# KUBODriver_Bridge.net
KiCad netlist of a schematic drawn in Altium Designer
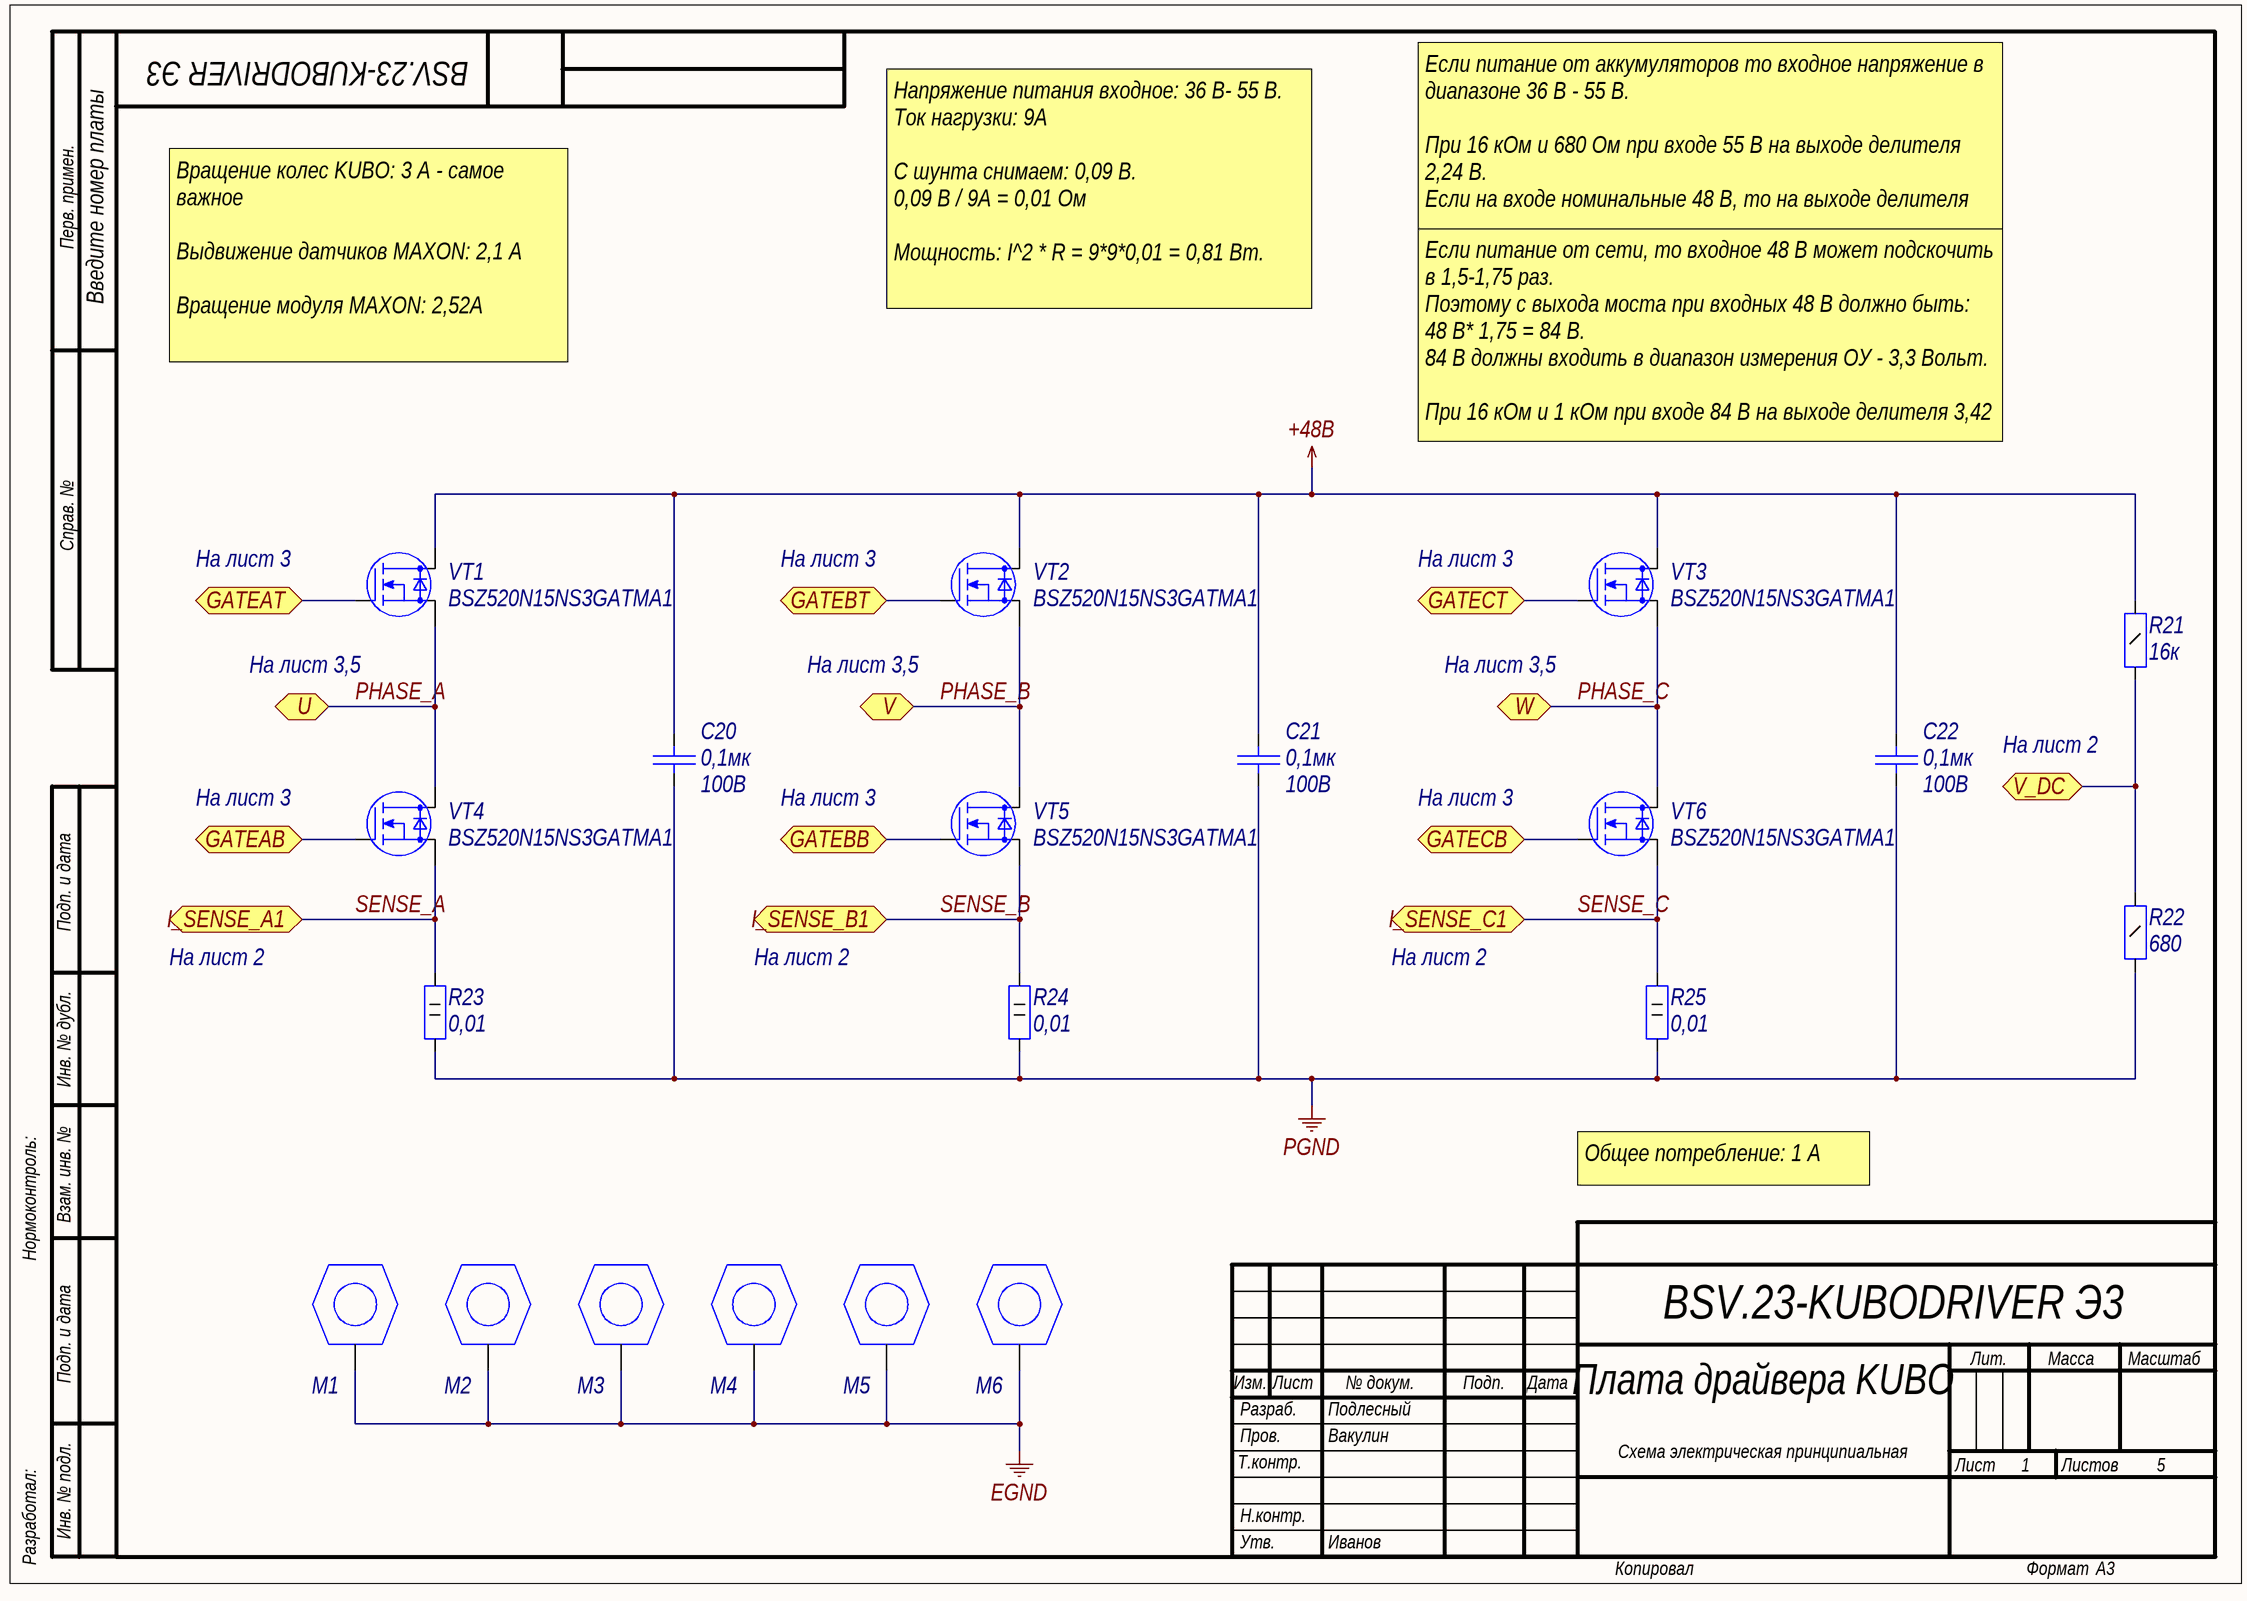
[diagram p0: KUBODriver_Bridge.SchDoc]

(export (version "E")
  (design (tool "Eeschema 10.0.6"))
  (components
    (comp (ref "C20")
      (value "0,1мк")
      (footprint "C1206")
      (description "Конденсатор")
      (fields (field (name "VOLTAGE") "100В") (field (name "PART NUMBER") "GRM31C5C2A104JA01L "))
      (libsource (lib "MOP44") (part "Capacitor"))
    )
    (comp (ref "C21")
      (value "0,1мк")
      (footprint "C1206")
      (description "Конденсатор")
      (fields (field (name "VOLTAGE") "100В") (field (name "PART NUMBER") "GRM31C5C2A104JA01L "))
      (libsource (lib "MOP44") (part "Capacitor"))
    )
    (comp (ref "C22")
      (value "0,1мк")
      (footprint "C1206")
      (description "Конденсатор")
      (fields (field (name "VOLTAGE") "100В") (field (name "PART NUMBER") "GRM31C5C2A104JA01L "))
      (libsource (lib "MOP44") (part "Capacitor"))
    )
    (comp (ref "M1") (value "SCREW") (footprint "SCREW3") (libsource (lib "MOP44") (part "SCREW")))
    (comp (ref "M2") (value "SCREW") (footprint "SCREW3") (libsource (lib "MOP44") (part "SCREW")))
    (comp (ref "M3") (value "SCREW") (footprint "SCREW3") (libsource (lib "MOP44") (part "SCREW")))
    (comp (ref "M4") (value "SCREW") (footprint "SCREW3") (libsource (lib "MOP44") (part "SCREW")))
    (comp (ref "M5") (value "SCREW") (footprint "SCREW3") (libsource (lib "MOP44") (part "SCREW")))
    (comp (ref "M6") (value "SCREW") (footprint "SCREW3") (libsource (lib "MOP44") (part "SCREW")))
    (comp (ref "R21")
      (value "16к")
      (footprint "R1206")
      (description "Резистор")
      (fields (field (name "PART NUMBER") "RC1206FR-0716KL") (field (name "POWER") "0,25Вт"))
      (libsource (lib "MOP44") (part "Resistor_0,25Вт"))
    )
    (comp (ref "R22")
      (value "680")
      (footprint "R1206")
      (description "Резистор")
      (fields (field (name "PART NUMBER") "RC1206FR-07680RL") (field (name "POWER") "0,25Вт"))
      (libsource (lib "MOP44") (part "Resistor_0,25Вт"))
    )
    (comp (ref "R23")
      (value "0,01")
      (footprint "R2512")
      (description "Резистор")
      (fields (field (name "PART NUMBER") "CRA2512-FZ-R010ELF") (field (name "POWER") "2Вт"))
      (libsource (lib "MOP44") (part "Resistor_2Вт"))
    )
    (comp (ref "R24")
      (value "0,01")
      (footprint "R2512")
      (description "Резистор")
      (fields (field (name "PART NUMBER") "CRA2512-FZ-R010ELF") (field (name "POWER") "2Вт"))
      (libsource (lib "MOP44") (part "Resistor_2Вт"))
    )
    (comp (ref "R25")
      (value "0,01")
      (footprint "R2512")
      (description "Резистор")
      (fields (field (name "PART NUMBER") "CRA2512-FZ-R010ELF") (field (name "POWER") "2Вт"))
      (libsource (lib "MOP44") (part "Resistor_2Вт"))
    )
    (comp (ref "VT1")
      (value "N-MOSFET")
      (footprint "TSDSON8")
      (fields
        (field (name "PART NUMBER") "BSZ520N15NS3GATMA1")
        (field (name "MANUFACTURER") "Infineon Technologies")
      )
      (libsource (lib "MOP44") (part "N-MOSFET"))
    )
    (comp (ref "VT2")
      (value "N-MOSFET")
      (footprint "TSDSON8")
      (fields
        (field (name "PART NUMBER") "BSZ520N15NS3GATMA1")
        (field (name "MANUFACTURER") "Infineon Technologies")
      )
      (libsource (lib "MOP44") (part "N-MOSFET"))
    )
    (comp (ref "VT3")
      (value "N-MOSFET")
      (footprint "TSDSON8")
      (fields
        (field (name "PART NUMBER") "BSZ520N15NS3GATMA1")
        (field (name "MANUFACTURER") "Infineon Technologies")
      )
      (libsource (lib "MOP44") (part "N-MOSFET"))
    )
    (comp (ref "VT4")
      (value "N-MOSFET")
      (footprint "TSDSON8")
      (fields
        (field (name "PART NUMBER") "BSZ520N15NS3GATMA1")
        (field (name "MANUFACTURER") "Infineon Technologies")
      )
      (libsource (lib "MOP44") (part "N-MOSFET"))
    )
    (comp (ref "VT5")
      (value "N-MOSFET")
      (footprint "TSDSON8")
      (fields
        (field (name "PART NUMBER") "BSZ520N15NS3GATMA1")
        (field (name "MANUFACTURER") "Infineon Technologies")
      )
      (libsource (lib "MOP44") (part "N-MOSFET"))
    )
    (comp (ref "VT6")
      (value "N-MOSFET")
      (footprint "TSDSON8")
      (fields
        (field (name "PART NUMBER") "BSZ520N15NS3GATMA1")
        (field (name "MANUFACTURER") "Infineon Technologies")
      )
      (libsource (lib "MOP44") (part "N-MOSFET"))
    )
  )
  (nets
    (net (code "1") (name "+48B") (class "Default")
      (node (ref "C20") (pin "2") (pinfunction "2_2") (pintype "passive"))
      (node (ref "C21") (pin "2") (pinfunction "2_2") (pintype "passive"))
      (node (ref "C22") (pin "2") (pinfunction "2_2") (pintype "passive"))
      (node (ref "R21") (pin "2") (pinfunction "2_2") (pintype "passive"))
      (node (ref "VT1") (pin "2") (pinfunction "D_2") (pintype "passive"))
      (node (ref "VT2") (pin "2") (pinfunction "D_2") (pintype "passive"))
      (node (ref "VT3") (pin "2") (pinfunction "D_2") (pintype "passive"))
    )
    (net (code "2") (name "/GATEAB") (class "Default")
      (node (ref "VT4") (pin "1") (pinfunction "G_1") (pintype "passive"))
    )
    (net (code "3") (name "/GATEAT") (class "Default")
      (node (ref "VT1") (pin "1") (pinfunction "G_1") (pintype "passive"))
    )
    (net (code "4") (name "/GATEBB") (class "Default")
      (node (ref "VT5") (pin "1") (pinfunction "G_1") (pintype "passive"))
    )
    (net (code "5") (name "/GATEBT") (class "Default")
      (node (ref "VT2") (pin "1") (pinfunction "G_1") (pintype "passive"))
    )
    (net (code "6") (name "/GATECB") (class "Default")
      (node (ref "VT6") (pin "1") (pinfunction "G_1") (pintype "passive"))
    )
    (net (code "7") (name "/GATECT") (class "Default")
      (node (ref "VT3") (pin "1") (pinfunction "G_1") (pintype "passive"))
    )
    (net (code "8") (name "/PHASE_A") (class "Default")
      (node (ref "VT1") (pin "3") (pinfunction "S_3") (pintype "passive"))
      (node (ref "VT4") (pin "2") (pinfunction "D_2") (pintype "passive"))
    )
    (net (code "9") (name "/PHASE_B") (class "Default")
      (node (ref "VT2") (pin "3") (pinfunction "S_3") (pintype "passive"))
      (node (ref "VT5") (pin "2") (pinfunction "D_2") (pintype "passive"))
    )
    (net (code "10") (name "/PHASE_C") (class "Default")
      (node (ref "VT3") (pin "3") (pinfunction "S_3") (pintype "passive"))
      (node (ref "VT6") (pin "2") (pinfunction "D_2") (pintype "passive"))
    )
    (net (code "11") (name "/SENSE_A") (class "Default")
      (node (ref "R23") (pin "2") (pinfunction "5_2") (pintype "passive"))
      (node (ref "VT4") (pin "3") (pinfunction "S_3") (pintype "passive"))
    )
    (net (code "12") (name "/SENSE_B") (class "Default")
      (node (ref "R24") (pin "2") (pinfunction "5_2") (pintype "passive"))
      (node (ref "VT5") (pin "3") (pinfunction "S_3") (pintype "passive"))
    )
    (net (code "13") (name "/SENSE_C") (class "Default")
      (node (ref "R25") (pin "2") (pinfunction "5_2") (pintype "passive"))
      (node (ref "VT6") (pin "3") (pinfunction "S_3") (pintype "passive"))
    )
    (net (code "14") (name "/V_DC") (class "Default")
      (node (ref "R21") (pin "1") (pinfunction "1_1") (pintype "passive"))
      (node (ref "R22") (pin "2") (pinfunction "2_2") (pintype "passive"))
    )
    (net (code "15") (name "EGND") (class "Default")
      (node (ref "M1") (pin "1") (pinfunction "1_1") (pintype "passive"))
      (node (ref "M2") (pin "1") (pinfunction "1_1") (pintype "passive"))
      (node (ref "M3") (pin "1") (pinfunction "1_1") (pintype "passive"))
      (node (ref "M4") (pin "1") (pinfunction "1_1") (pintype "passive"))
      (node (ref "M5") (pin "1") (pinfunction "1_1") (pintype "passive"))
      (node (ref "M6") (pin "1") (pinfunction "1_1") (pintype "passive"))
    )
    (net (code "16") (name "PGND") (class "Default")
      (node (ref "C20") (pin "1") (pinfunction "1_1") (pintype "passive"))
      (node (ref "C21") (pin "1") (pinfunction "1_1") (pintype "passive"))
      (node (ref "C22") (pin "1") (pinfunction "1_1") (pintype "passive"))
      (node (ref "R22") (pin "1") (pinfunction "1_1") (pintype "passive"))
      (node (ref "R23") (pin "1") (pinfunction "1_1") (pintype "passive"))
      (node (ref "R24") (pin "1") (pinfunction "1_1") (pintype "passive"))
      (node (ref "R25") (pin "1") (pinfunction "1_1") (pintype "passive"))
    )
  )
)
